# arduino.net
KiCad netlist of a schematic drawn in EAGLE
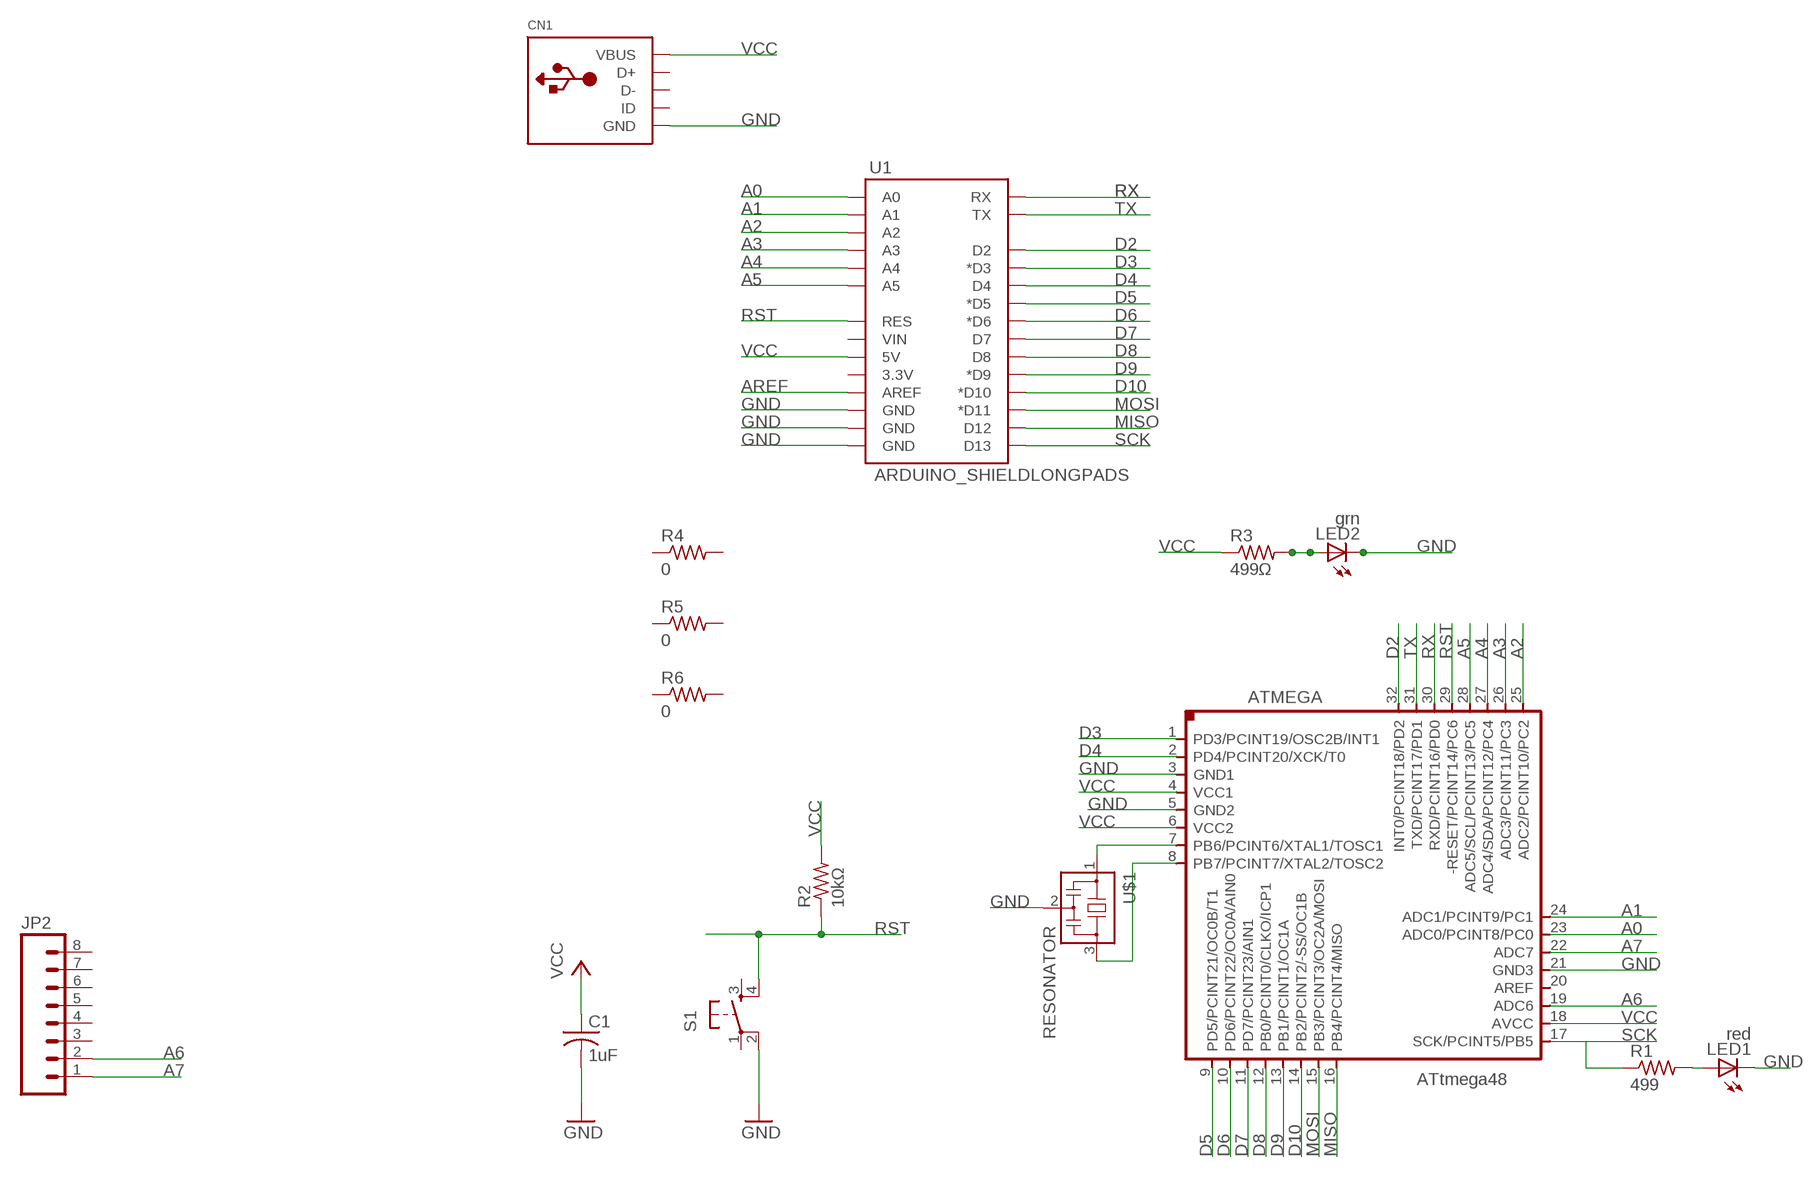
[diagram p0: schematic, sheet 1]

(export (version "E")
  (design (tool "Eeschema 10.0.6"))
  (components
    (comp (ref "ATMEGA")
      (value "328p-au")
      (footprint "eagle-import:TQFP32-08")
      (libsource (lib "eagle-import") (part "ATMEGA48TQFP"))
    )
    (comp (ref "C1")
      (value "1uF")
      (footprint "eagle-import:C1206")
      (libsource (lib "eagle-import") (part "C-USC1206"))
    )
    (comp (ref "CN1")
      (value "USBMINIB")
      (footprint "eagle-import:USB-MINIB")
      (libsource (lib "eagle-import") (part "USBMINIB"))
    )
    (comp (ref "JP2")
      (value "M08LOCK_LONGPADS")
      (footprint "eagle-import:1X08_LOCK_LONGPADS")
      (libsource (lib "eagle-import") (part "M08LOCK_LONGPADS"))
    )
    (comp (ref "LED1")
      (value "red")
      (footprint "eagle-import:CHIPLED_1206")
      (libsource (lib "eagle-import") (part "LEDCHIPLED_1206"))
    )
    (comp (ref "LED2")
      (value "grn")
      (footprint "eagle-import:CHIPLED_1206")
      (libsource (lib "eagle-import") (part "LEDCHIPLED_1206"))
    )
    (comp (ref "R1")
      (value "499")
      (footprint "eagle-import:R1206")
      (libsource (lib "eagle-import") (part "R-US_R1206"))
    )
    (comp (ref "R2")
      (value "10kΩ")
      (footprint "eagle-import:M1206")
      (libsource (lib "eagle-import") (part "R-US_M1206"))
    )
    (comp (ref "R3")
      (value "499Ω")
      (footprint "eagle-import:M1206")
      (libsource (lib "eagle-import") (part "R-US_M1206"))
    )
    (comp (ref "R4")
      (value "0")
      (footprint "eagle-import:M1206")
      (libsource (lib "eagle-import") (part "R-US_M1206"))
    )
    (comp (ref "R5")
      (value "0")
      (footprint "eagle-import:M1206")
      (libsource (lib "eagle-import") (part "R-US_M1206"))
    )
    (comp (ref "R6")
      (value "0")
      (footprint "eagle-import:M1206")
      (libsource (lib "eagle-import") (part "R-US_M1206"))
    )
    (comp (ref "S1")
      (value "6MM_SWITCH6MM_SWITCH")
      (footprint "eagle-import:6MM_SWITCH")
      (libsource (lib "eagle-import") (part "6MM_SWITCH6MM_SWITCH"))
    )
    (comp (ref "U$1")
      (value "RESONATOR")
      (footprint "eagle-import:EFOBM")
      (libsource (lib "eagle-import") (part "RESONATOR"))
    )
    (comp (ref "U1")
      (value "ARDUINO_SHIELDLONGPADS")
      (footprint "eagle-import:DUEMILANOVE_SHIELD_LONGPADS")
      (libsource (lib "eagle-import") (part "ARDUINO_SHIELDLONGPADS"))
    )
  )
  (nets
    (net (code "1") (name "/A0") (class "Default")
      (node (ref "ATMEGA") (pin "23") (pinfunction "ADC0/PCINT8/PC0_23") (pintype "bidirectional"))
      (node (ref "U1") (pin "A0") (pinfunction "A0_A0") (pintype "bidirectional"))
    )
    (net (code "2") (name "/A1") (class "Default")
      (node (ref "ATMEGA") (pin "24") (pinfunction "ADC1/PCINT9/PC1_24") (pintype "bidirectional"))
      (node (ref "U1") (pin "A1") (pinfunction "A1_A1") (pintype "bidirectional"))
    )
    (net (code "3") (name "/A2") (class "Default")
      (node (ref "ATMEGA") (pin "25") (pinfunction "ADC2/PCINT10/PC2_25") (pintype "bidirectional"))
      (node (ref "U1") (pin "A2") (pinfunction "A2_A2") (pintype "bidirectional"))
    )
    (net (code "4") (name "/A3") (class "Default")
      (node (ref "ATMEGA") (pin "26") (pinfunction "ADC3/PCINT11/PC3_26") (pintype "bidirectional"))
      (node (ref "U1") (pin "A3") (pinfunction "A3_A3") (pintype "bidirectional"))
    )
    (net (code "5") (name "/A4") (class "Default")
      (node (ref "ATMEGA") (pin "27") (pinfunction "ADC4/SDA/PCINT12/PC4_27") (pintype "bidirectional"))
      (node (ref "U1") (pin "A4") (pinfunction "A4_A4") (pintype "bidirectional"))
    )
    (net (code "6") (name "/A5") (class "Default")
      (node (ref "ATMEGA") (pin "28") (pinfunction "ADC5/SCL/PCINT13/PC5_28") (pintype "bidirectional"))
      (node (ref "U1") (pin "A5") (pinfunction "A5_A5") (pintype "bidirectional"))
    )
    (net (code "7") (name "/A6") (class "Default")
      (node (ref "ATMEGA") (pin "19") (pinfunction "ADC6_19") (pintype "bidirectional"))
      (node (ref "JP2") (pin "2") (pinfunction "2_2") (pintype "passive"))
    )
    (net (code "8") (name "/A7") (class "Default")
      (node (ref "ATMEGA") (pin "22") (pinfunction "ADC7_22") (pintype "bidirectional"))
      (node (ref "JP2") (pin "1") (pinfunction "1_1") (pintype "passive"))
    )
    (net (code "9") (name "/AREF") (class "Default")
      (node (ref "U1") (pin "AREF") (pinfunction "AREF_AREF") (pintype "bidirectional"))
    )
    (net (code "10") (name "/D2") (class "Default")
      (node (ref "ATMEGA") (pin "32") (pinfunction "INT0/PCINT18/PD2_32") (pintype "bidirectional"))
      (node (ref "U1") (pin "D2") (pinfunction "D2_D2") (pintype "bidirectional"))
    )
    (net (code "11") (name "/D3") (class "Default")
      (node (ref "ATMEGA") (pin "1") (pinfunction "PD3/PCINT19/OSC2B/INT1_1") (pintype "bidirectional"))
      (node (ref "U1") (pin "D3") (pinfunction "*D3_D3") (pintype "bidirectional"))
    )
    (net (code "12") (name "/D4") (class "Default")
      (node (ref "ATMEGA") (pin "2") (pinfunction "PD4/PCINT20/XCK/T0_2") (pintype "bidirectional"))
      (node (ref "U1") (pin "D4") (pinfunction "D4_D4") (pintype "bidirectional"))
    )
    (net (code "13") (name "/D5") (class "Default")
      (node (ref "ATMEGA") (pin "9") (pinfunction "PD5/PCINT21/OC0B/T1_9") (pintype "bidirectional"))
      (node (ref "U1") (pin "D5") (pinfunction "*D5_D5") (pintype "bidirectional"))
    )
    (net (code "14") (name "/D6") (class "Default")
      (node (ref "ATMEGA") (pin "10") (pinfunction "PD6/PCINT22/OC0A/AIN0_10") (pintype "bidirectional"))
      (node (ref "U1") (pin "D6") (pinfunction "*D6_D6") (pintype "bidirectional"))
    )
    (net (code "15") (name "/D7") (class "Default")
      (node (ref "ATMEGA") (pin "11") (pinfunction "PD7/PCINT23/AIN1_11") (pintype "bidirectional"))
      (node (ref "U1") (pin "D7") (pinfunction "D7_D7") (pintype "bidirectional"))
    )
    (net (code "16") (name "/D8") (class "Default")
      (node (ref "ATMEGA") (pin "12") (pinfunction "PB0/PCINT0/CLKO/ICP1_12") (pintype "bidirectional"))
      (node (ref "U1") (pin "D8") (pinfunction "D8_D8") (pintype "bidirectional"))
    )
    (net (code "17") (name "/D9") (class "Default")
      (node (ref "ATMEGA") (pin "13") (pinfunction "PB1/PCINT1/OC1A_13") (pintype "bidirectional"))
      (node (ref "U1") (pin "D9") (pinfunction "*D9_D9") (pintype "bidirectional"))
    )
    (net (code "18") (name "/D10") (class "Default")
      (node (ref "ATMEGA") (pin "14") (pinfunction "PB2/PCINT2/-SS/OC1B_14") (pintype "bidirectional"))
      (node (ref "U1") (pin "D10") (pinfunction "*D10_D10") (pintype "bidirectional"))
    )
    (net (code "19") (name "/MISO") (class "Default")
      (node (ref "ATMEGA") (pin "16") (pinfunction "PB4/PCINT4/MISO_16") (pintype "bidirectional"))
      (node (ref "U1") (pin "D12") (pinfunction "D12_D12") (pintype "bidirectional"))
    )
    (net (code "20") (name "/MOSI") (class "Default")
      (node (ref "ATMEGA") (pin "15") (pinfunction "PB3/PCINT3/OC2A/MOSI_15") (pintype "bidirectional"))
      (node (ref "U1") (pin "D11") (pinfunction "*D11_D11") (pintype "bidirectional"))
    )
    (net (code "21") (name "/RST") (class "Default")
      (node (ref "ATMEGA") (pin "29") (pinfunction "-RESET/PCINT14/PC6_29") (pintype "bidirectional"))
      (node (ref "R2") (pin "1") (pinfunction "1_1") (pintype "passive"))
      (node (ref "S1") (pin "4") (pinfunction "S1_4") (pintype "passive"))
      (node (ref "U1") (pin "RES") (pinfunction "RES_RES") (pintype "bidirectional"))
    )
    (net (code "22") (name "/RX") (class "Default")
      (node (ref "ATMEGA") (pin "30") (pinfunction "RXD/PCINT16/PD0_30") (pintype "bidirectional"))
      (node (ref "U1") (pin "RX") (pinfunction "RX_RX") (pintype "bidirectional"))
    )
    (net (code "23") (name "/SCK") (class "Default")
      (node (ref "ATMEGA") (pin "17") (pinfunction "SCK/PCINT5/PB5_17") (pintype "bidirectional"))
      (node (ref "R1") (pin "1") (pinfunction "1_1") (pintype "passive"))
      (node (ref "U1") (pin "D13") (pinfunction "D13_D13") (pintype "bidirectional"))
    )
    (net (code "24") (name "/TX") (class "Default")
      (node (ref "ATMEGA") (pin "31") (pinfunction "TXD/PCINT17/PD1_31") (pintype "bidirectional"))
      (node (ref "U1") (pin "TX") (pinfunction "TX_TX") (pintype "bidirectional"))
    )
    (net (code "25") (name "GND") (class "Default")
      (node (ref "ATMEGA") (pin "21") (pinfunction "GND3_21") (pintype "bidirectional"))
      (node (ref "ATMEGA") (pin "3") (pinfunction "GND1_3") (pintype "bidirectional"))
      (node (ref "ATMEGA") (pin "5") (pinfunction "GND2_5") (pintype "bidirectional"))
      (node (ref "C1") (pin "2") (pinfunction "2_2") (pintype "passive"))
      (node (ref "CN1") (pin "GND") (pinfunction "GND_GND") (pintype "power_in"))
      (node (ref "LED1") (pin "C") (pinfunction "C_C") (pintype "passive"))
      (node (ref "LED2") (pin "C") (pinfunction "C_C") (pintype "passive"))
      (node (ref "S1") (pin "2") (pinfunction "P1_2") (pintype "passive"))
      (node (ref "U$1") (pin "2") (pinfunction "2_2") (pintype "passive"))
      (node (ref "U1") (pin "GND@0") (pinfunction "GND_GND@0") (pintype "bidirectional"))
      (node (ref "U1") (pin "GND@1") (pinfunction "GND_GND@1") (pintype "bidirectional"))
      (node (ref "U1") (pin "GND@2") (pinfunction "GND_GND@2") (pintype "bidirectional"))
    )
    (net (code "26") (name "Net-(ATMEGA-PB6{slash}PCINT6{slash}XTAL1{slash}TOSC1)") (class "Default")
      (node (ref "ATMEGA") (pin "7") (pinfunction "PB6/PCINT6/XTAL1/TOSC1_7") (pintype "bidirectional"))
      (node (ref "U$1") (pin "1") (pinfunction "1_1") (pintype "passive"))
    )
    (net (code "27") (name "Net-(ATMEGA-PB7{slash}PCINT7{slash}XTAL2{slash}TOSC2)") (class "Default")
      (node (ref "ATMEGA") (pin "8") (pinfunction "PB7/PCINT7/XTAL2/TOSC2_8") (pintype "bidirectional"))
      (node (ref "U$1") (pin "3") (pinfunction "3_3") (pintype "passive"))
    )
    (net (code "28") (name "Net-(LED1-PadA)") (class "Default")
      (node (ref "LED1") (pin "A") (pinfunction "A_A") (pintype "passive"))
      (node (ref "R1") (pin "2") (pinfunction "2_2") (pintype "passive"))
    )
    (net (code "29") (name "Net-(LED2-PadA)") (class "Default")
      (node (ref "LED2") (pin "A") (pinfunction "A_A") (pintype "passive"))
      (node (ref "R3") (pin "2") (pinfunction "2_2") (pintype "passive"))
    )
    (net (code "30") (name "VCC") (class "Default")
      (node (ref "ATMEGA") (pin "18") (pinfunction "AVCC_18") (pintype "bidirectional"))
      (node (ref "ATMEGA") (pin "4") (pinfunction "VCC1_4") (pintype "bidirectional"))
      (node (ref "ATMEGA") (pin "6") (pinfunction "VCC2_6") (pintype "bidirectional"))
      (node (ref "C1") (pin "1") (pinfunction "1_1") (pintype "passive"))
      (node (ref "CN1") (pin "VBUS") (pinfunction "VBUS_VBUS") (pintype "power_in"))
      (node (ref "R2") (pin "2") (pinfunction "2_2") (pintype "passive"))
      (node (ref "R3") (pin "1") (pinfunction "1_1") (pintype "passive"))
      (node (ref "U1") (pin "5V") (pinfunction "5V_5V") (pintype "bidirectional"))
    )
    (net (code "31") (name "unconnected-(ATMEGA-AREF-Pad20)") (class "Default")
      (node (ref "ATMEGA") (pin "20") (pinfunction "AREF_20") (pintype "bidirectional"))
    )
    (net (code "32") (name "unconnected-(CN1-PadD+)") (class "Default")
      (node (ref "CN1") (pin "D+") (pinfunction "D+_D+") (pintype "bidirectional"))
    )
    (net (code "33") (name "unconnected-(CN1-PadD-)") (class "Default")
      (node (ref "CN1") (pin "D-") (pinfunction "D-_D-") (pintype "bidirectional"))
    )
    (net (code "34") (name "unconnected-(CN1-PadID)") (class "Default")
      (node (ref "CN1") (pin "ID") (pinfunction "ID_ID") (pintype "bidirectional"))
    )
    (net (code "35") (name "unconnected-(JP2-Pad3)") (class "Default")
      (node (ref "JP2") (pin "3") (pinfunction "3_3") (pintype "passive"))
    )
    (net (code "36") (name "unconnected-(JP2-Pad4)") (class "Default")
      (node (ref "JP2") (pin "4") (pinfunction "4_4") (pintype "passive"))
    )
    (net (code "37") (name "unconnected-(JP2-Pad5)") (class "Default")
      (node (ref "JP2") (pin "5") (pinfunction "5_5") (pintype "passive"))
    )
    (net (code "38") (name "unconnected-(JP2-Pad6)") (class "Default")
      (node (ref "JP2") (pin "6") (pinfunction "6_6") (pintype "passive"))
    )
    (net (code "39") (name "unconnected-(JP2-Pad7)") (class "Default")
      (node (ref "JP2") (pin "7") (pinfunction "7_7") (pintype "passive"))
    )
    (net (code "40") (name "unconnected-(JP2-Pad8)") (class "Default")
      (node (ref "JP2") (pin "8") (pinfunction "8_8") (pintype "passive"))
    )
    (net (code "41") (name "unconnected-(R4-Pad1)") (class "Default")
      (node (ref "R4") (pin "1") (pinfunction "1_1") (pintype "passive"))
    )
    (net (code "42") (name "unconnected-(R4-Pad2)") (class "Default")
      (node (ref "R4") (pin "2") (pinfunction "2_2") (pintype "passive"))
    )
    (net (code "43") (name "unconnected-(R5-Pad1)") (class "Default")
      (node (ref "R5") (pin "1") (pinfunction "1_1") (pintype "passive"))
    )
    (net (code "44") (name "unconnected-(R5-Pad2)") (class "Default")
      (node (ref "R5") (pin "2") (pinfunction "2_2") (pintype "passive"))
    )
    (net (code "45") (name "unconnected-(R6-Pad1)") (class "Default")
      (node (ref "R6") (pin "1") (pinfunction "1_1") (pintype "passive"))
    )
    (net (code "46") (name "unconnected-(R6-Pad2)") (class "Default")
      (node (ref "R6") (pin "2") (pinfunction "2_2") (pintype "passive"))
    )
    (net (code "47") (name "unconnected-(S1-P-Pad1)") (class "Default")
      (node (ref "S1") (pin "1") (pinfunction "P_1") (pintype "passive"))
    )
    (net (code "48") (name "unconnected-(S1-S-Pad3)") (class "Default")
      (node (ref "S1") (pin "3") (pinfunction "S_3") (pintype "passive"))
    )
    (net (code "49") (name "unconnected-(U1-Pad3.3V)") (class "Default")
      (node (ref "U1") (pin "3.3V") (pinfunction "3.3V_3.3V") (pintype "bidirectional"))
    )
    (net (code "50") (name "unconnected-(U1-PadVIN)") (class "Default")
      (node (ref "U1") (pin "VIN") (pinfunction "VIN_VIN") (pintype "bidirectional"))
    )
  )
)
